# Power.net
KiCad netlist of a schematic drawn in Altium Designer
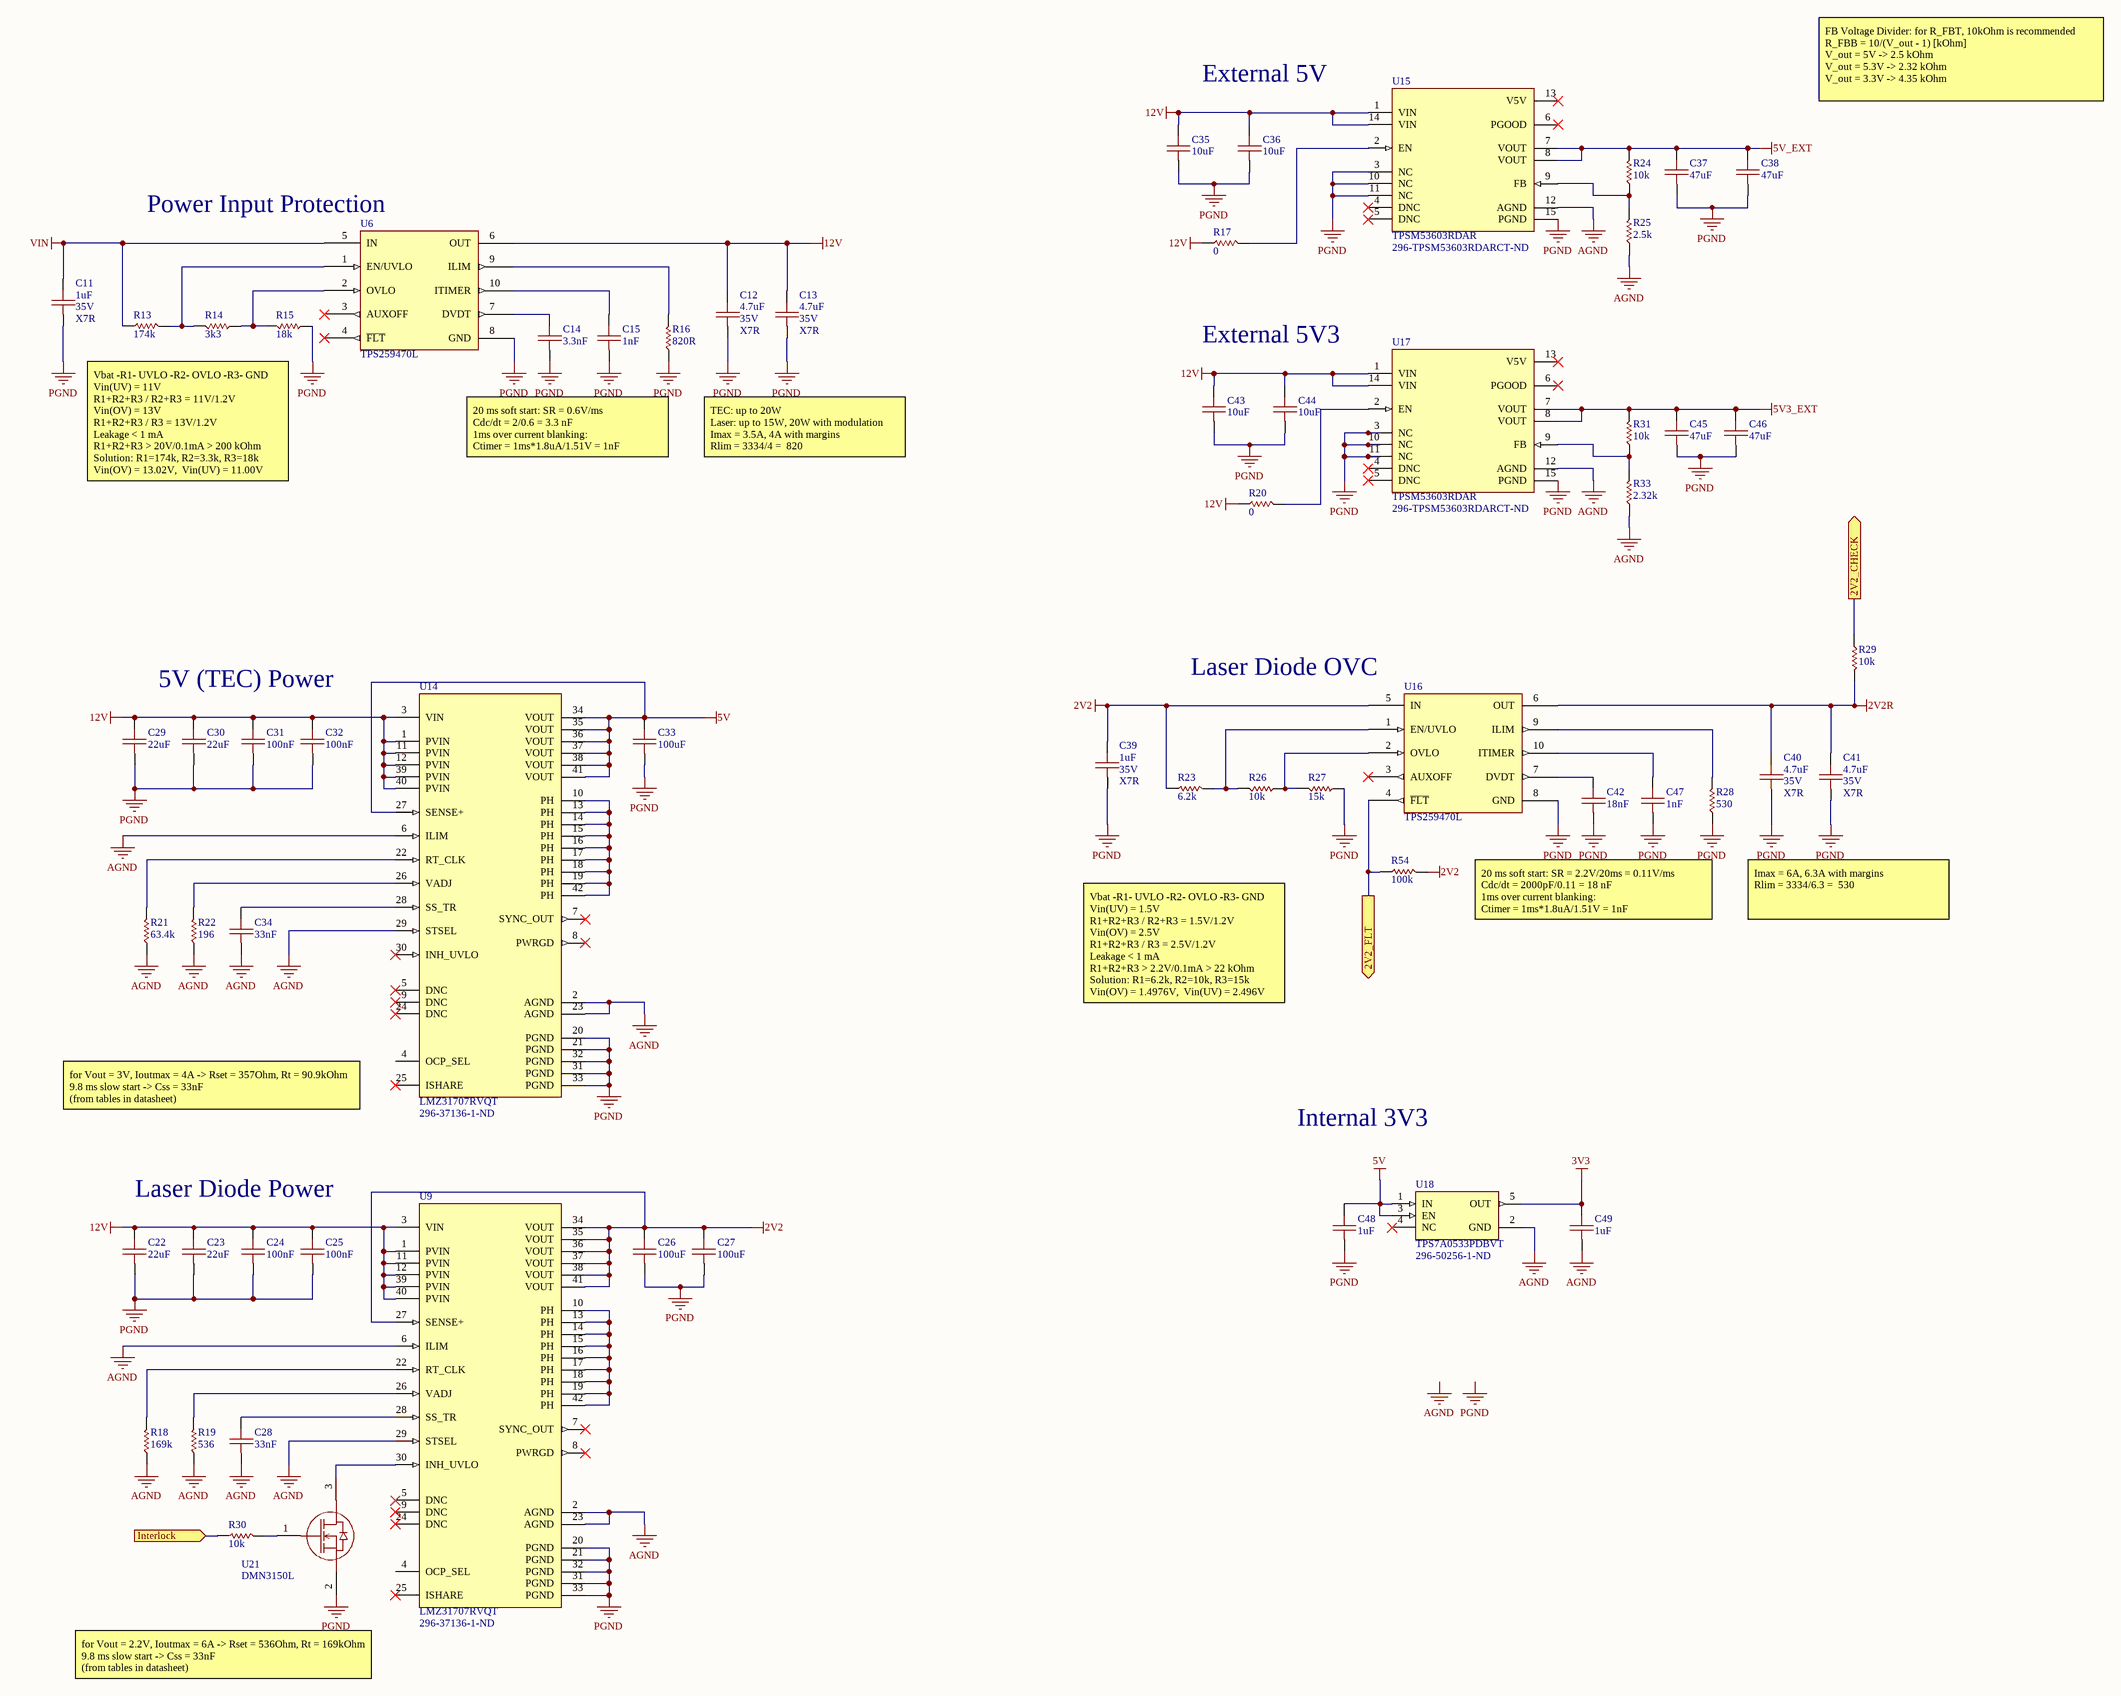
[diagram p0: Power.SchDoc]

(export (version "E")
  (design (tool "Eeschema 10.0.6"))
  (components
    (comp (ref "C11")
      (value "1uF")
      (footprint "0805 B")
      (description "805 Capacitor")
      (fields (field (name "VOLTAGE") "35V") (field (name "TYPE") "X7R"))
      (libsource (lib "PSSL3") (part "CAP 0805"))
    )
    (comp (ref "C12")
      (value "4.7uF")
      (footprint "0805 B")
      (description "805 Capacitor")
      (fields (field (name "VOLTAGE") "35V") (field (name "TYPE") "X7R"))
      (libsource (lib "PSSL3") (part "CAP 0805"))
    )
    (comp (ref "C13")
      (value "4.7uF")
      (footprint "0805 B")
      (description "805 Capacitor")
      (fields (field (name "VOLTAGE") "35V") (field (name "TYPE") "X7R"))
      (libsource (lib "PSSL3") (part "CAP 0805"))
    )
    (comp (ref "C14")
      (value "3.3nF")
      (footprint "0603 B")
      (description "603 Capacitor")
      (libsource (lib "PSSL3") (part "CAP 0603"))
    )
    (comp (ref "C15")
      (value "1nF")
      (footprint "0603 B")
      (description "603 Capacitor")
      (libsource (lib "PSSL3") (part "CAP 0603"))
    )
    (comp (ref "C22")
      (value "22uF")
      (footprint "1210")
      (description "1210 Capacitor")
      (libsource (lib "PSSL3") (part "CAP 1210"))
    )
    (comp (ref "C23")
      (value "22uF")
      (footprint "1210")
      (description "1210 Capacitor")
      (libsource (lib "PSSL3") (part "CAP 1210"))
    )
    (comp (ref "C24")
      (value "100nF")
      (footprint "0603 B")
      (description "603 Capacitor")
      (libsource (lib "PSSL3") (part "CAP 0603"))
    )
    (comp (ref "C25")
      (value "100nF")
      (footprint "0603 B")
      (description "603 Capacitor")
      (libsource (lib "PSSL3") (part "CAP 0603"))
    )
    (comp (ref "C26")
      (value "100uF")
      (footprint "1206 B")
      (description "1206 Capacitor")
      (libsource (lib "PSSL3") (part "CAP 1206"))
    )
    (comp (ref "C27")
      (value "100uF")
      (footprint "1206 B")
      (description "1206 Capacitor")
      (libsource (lib "PSSL3") (part "CAP 1206"))
    )
    (comp (ref "C28")
      (value "33nF")
      (footprint "0603 B")
      (description "603 Capacitor")
      (libsource (lib "PSSL3") (part "CAP 0603"))
    )
    (comp (ref "C29")
      (value "22uF")
      (footprint "1210")
      (description "1210 Capacitor")
      (libsource (lib "PSSL3") (part "CAP 1210"))
    )
    (comp (ref "C30")
      (value "22uF")
      (footprint "1210")
      (description "1210 Capacitor")
      (libsource (lib "PSSL3") (part "CAP 1210"))
    )
    (comp (ref "C31")
      (value "100nF")
      (footprint "0603 B")
      (description "603 Capacitor")
      (libsource (lib "PSSL3") (part "CAP 0603"))
    )
    (comp (ref "C32")
      (value "100nF")
      (footprint "0603 B")
      (description "603 Capacitor")
      (libsource (lib "PSSL3") (part "CAP 0603"))
    )
    (comp (ref "C33")
      (value "100uF")
      (footprint "1206 B")
      (description "1206 Capacitor")
      (libsource (lib "PSSL3") (part "CAP 1206"))
    )
    (comp (ref "C34")
      (value "33nF")
      (footprint "0603 B")
      (description "603 Capacitor")
      (libsource (lib "PSSL3") (part "CAP 0603"))
    )
    (comp (ref "C35")
      (value "10uF")
      (footprint "0603 B")
      (description "603 Capacitor")
      (libsource (lib "PSSL3") (part "CAP 0603"))
    )
    (comp (ref "C36")
      (value "10uF")
      (footprint "0603 B")
      (description "603 Capacitor")
      (libsource (lib "PSSL3") (part "CAP 0603"))
    )
    (comp (ref "C37")
      (value "47uF")
      (footprint "0603 B")
      (description "603 Capacitor")
      (libsource (lib "PSSL3") (part "CAP 0603"))
    )
    (comp (ref "C38")
      (value "47uF")
      (footprint "0603 B")
      (description "603 Capacitor")
      (libsource (lib "PSSL3") (part "CAP 0603"))
    )
    (comp (ref "C39")
      (value "1uF")
      (footprint "0805 B")
      (description "805 Capacitor")
      (fields (field (name "VOLTAGE") "35V") (field (name "TYPE") "X7R"))
      (libsource (lib "PSSL3") (part "CAP 0805"))
    )
    (comp (ref "C40")
      (value "4.7uF")
      (footprint "0805 B")
      (description "805 Capacitor")
      (fields (field (name "VOLTAGE") "35V") (field (name "TYPE") "X7R"))
      (libsource (lib "PSSL3") (part "CAP 0805"))
    )
    (comp (ref "C41")
      (value "4.7uF")
      (footprint "0805 B")
      (description "805 Capacitor")
      (fields (field (name "VOLTAGE") "35V") (field (name "TYPE") "X7R"))
      (libsource (lib "PSSL3") (part "CAP 0805"))
    )
    (comp (ref "C42")
      (value "18nF")
      (footprint "0603 B")
      (description "603 Capacitor")
      (libsource (lib "PSSL3") (part "CAP 0603"))
    )
    (comp (ref "C43")
      (value "10uF")
      (footprint "0603 B")
      (description "603 Capacitor")
      (libsource (lib "PSSL3") (part "CAP 0603"))
    )
    (comp (ref "C44")
      (value "10uF")
      (footprint "0603 B")
      (description "603 Capacitor")
      (libsource (lib "PSSL3") (part "CAP 0603"))
    )
    (comp (ref "C45")
      (value "47uF")
      (footprint "0603 B")
      (description "603 Capacitor")
      (libsource (lib "PSSL3") (part "CAP 0603"))
    )
    (comp (ref "C46")
      (value "47uF")
      (footprint "0603 B")
      (description "603 Capacitor")
      (libsource (lib "PSSL3") (part "CAP 0603"))
    )
    (comp (ref "C47")
      (value "1nF")
      (footprint "0603 B")
      (description "603 Capacitor")
      (libsource (lib "PSSL3") (part "CAP 0603"))
    )
    (comp (ref "C48")
      (value "1uF")
      (footprint "0603 B")
      (description "603 Capacitor")
      (libsource (lib "PSSL3") (part "CAP 0603"))
    )
    (comp (ref "C49")
      (value "1uF")
      (footprint "0603 B")
      (description "603 Capacitor")
      (libsource (lib "PSSL3") (part "CAP 0603"))
    )
    (comp (ref "R13")
      (value "174k")
      (footprint "0603")
      (description "603 Resistor")
      (libsource (lib "PSSL3") (part "RES 0603"))
    )
    (comp (ref "R14")
      (value "3k3")
      (footprint "0603")
      (description "603 Resistor")
      (libsource (lib "PSSL3") (part "RES 0603"))
    )
    (comp (ref "R15")
      (value "18k")
      (footprint "0603")
      (description "603 Resistor")
      (libsource (lib "PSSL3") (part "RES 0603"))
    )
    (comp (ref "R16")
      (value "820R")
      (footprint "0603")
      (description "603 Resistor")
      (libsource (lib "PSSL3") (part "RES 0603"))
    )
    (comp (ref "R17")
      (value "0")
      (footprint "0603")
      (description "603 Resistor")
      (libsource (lib "PSSL3") (part "RES 0603"))
    )
    (comp (ref "R18")
      (value "169k")
      (footprint "0805")
      (description "805 Resistor")
      (libsource (lib "PSSL3") (part "RES 0805"))
    )
    (comp (ref "R19")
      (value "536")
      (footprint "0805")
      (description "805 Resistor")
      (libsource (lib "PSSL3") (part "RES 0805"))
    )
    (comp (ref "R20")
      (value "0")
      (footprint "0603")
      (description "603 Resistor")
      (libsource (lib "PSSL3") (part "RES 0603"))
    )
    (comp (ref "R21")
      (value "63.4k")
      (footprint "0805")
      (description "805 Resistor")
      (libsource (lib "PSSL3") (part "RES 0805"))
    )
    (comp (ref "R22")
      (value "196")
      (footprint "0805")
      (description "805 Resistor")
      (libsource (lib "PSSL3") (part "RES 0805"))
    )
    (comp (ref "R23")
      (value "6.2k")
      (footprint "0603")
      (description "603 Resistor")
      (libsource (lib "PSSL3") (part "RES 0603"))
    )
    (comp (ref "R24")
      (value "10k")
      (footprint "0805")
      (description "805 Resistor")
      (libsource (lib "PSSL3") (part "RES 0805"))
    )
    (comp (ref "R25")
      (value "2.5k")
      (footprint "0805")
      (description "805 Resistor")
      (libsource (lib "PSSL3") (part "RES 0805"))
    )
    (comp (ref "R26")
      (value "10k")
      (footprint "0603")
      (description "603 Resistor")
      (libsource (lib "PSSL3") (part "RES 0603"))
    )
    (comp (ref "R27")
      (value "15k")
      (footprint "0603")
      (description "603 Resistor")
      (libsource (lib "PSSL3") (part "RES 0603"))
    )
    (comp (ref "R28")
      (value "530")
      (footprint "0603")
      (description "603 Resistor")
      (libsource (lib "PSSL3") (part "RES 0603"))
    )
    (comp (ref "R29")
      (value "10k")
      (footprint "0603")
      (description "603 Resistor")
      (libsource (lib "PSSL3") (part "RES 0603"))
    )
    (comp (ref "R30")
      (value "10k")
      (footprint "0603")
      (description "603 Resistor")
      (libsource (lib "PSSL3") (part "RES 0603"))
    )
    (comp (ref "R31")
      (value "10k")
      (footprint "0805")
      (description "805 Resistor")
      (libsource (lib "PSSL3") (part "RES 0805"))
    )
    (comp (ref "R33")
      (value "2.32k")
      (footprint "0805")
      (description "805 Resistor")
      (libsource (lib "PSSL3") (part "RES 0805"))
    )
    (comp (ref "R54")
      (value "100k")
      (footprint "0603")
      (description "603 Resistor")
      (libsource (lib "PSSL3") (part "RES 0603"))
    )
    (comp (ref "U6")
      (value "TPS259470L")
      (footprint "VQFN-HR 2x2")
      (description "2.7-23 V, 5.5 A, 28 mΩ True Reverse Current Blocking eFuse with Input Reverse Polarity Protection")
      (libsource (lib "PSSL3") (part "TPS259470L"))
    )
    (comp (ref "U9")
      (value "LMZ31707RVQT")
      (footprint "PB3QFN")
      (description "Non-Isolated DC/DC Converters 7A Power Module w/ 2.95V-17V Input")
      (fields
        (field (name "PARTNUMBER") "LMZ31707RVQR")
        (field (name "MANUFACTURER") "Texas Instruments")
        (field (name "SUPPLIER PART NUMBER 1") "296-37136-1-ND")
        (field (name "COPYRIGHT") "Copyright (C) 2018 Accelerated Designs. All rights reserved")
      )
      (libsource (lib "BeaconBoard") (part "LMZ31707RVQT"))
    )
    (comp (ref "U14")
      (value "LMZ31707RVQT")
      (footprint "PB3QFN")
      (description "Non-Isolated DC/DC Converters 7A Power Module w/ 2.95V-17V Input")
      (fields
        (field (name "PARTNUMBER") "LMZ31707RVQR")
        (field (name "MANUFACTURER") "Texas Instruments")
        (field (name "SUPPLIER PART NUMBER 1") "296-37136-1-ND")
        (field (name "COPYRIGHT") "Copyright (C) 2018 Accelerated Designs. All rights reserved")
      )
      (libsource (lib "BeaconBoard") (part "LMZ31707RVQT"))
    )
    (comp (ref "U15")
      (value "TPSM53603RDAR")
      (footprint "RDA0015A")
      (fields
        (field (name "MANUFACTURER") "Texas Instruments")
        (field (name "SUPPLIER PART NUMBER 1") "296-TPSM53603RDARCT-ND")
        (field (name "COPYRIGHT") "Copyright (C) 2018 Accelerated Designs. All rights reserved")
      )
      (libsource (lib "BeaconBoard") (part "TPSM53603RDAR"))
    )
    (comp (ref "U16")
      (value "TPS259470L")
      (footprint "VQFN-HR 2x2")
      (description "2.7-23 V, 5.5 A, 28 mΩ True Reverse Current Blocking eFuse with Input Reverse Polarity Protection")
      (libsource (lib "PSSL3") (part "TPS259470L"))
    )
    (comp (ref "U17")
      (value "TPSM53603RDAR")
      (footprint "RDA0015A")
      (fields
        (field (name "MANUFACTURER") "Texas Instruments")
        (field (name "SUPPLIER PART NUMBER 1") "296-TPSM53603RDARCT-ND")
        (field (name "COPYRIGHT") "Copyright (C) 2018 Accelerated Designs. All rights reserved")
      )
      (libsource (lib "BeaconBoard") (part "TPSM53603RDAR"))
    )
    (comp (ref "U18")
      (value "TPS7A0533PDBVT")
      (footprint "DBV0005A-MFG")
      (description "Linear Voltage Regulator IC Positive Fixed 1 Output 200mA SOT-23-5")
      (fields
        (field (name "PARTNUMBER") "TPS7A2050PDBVR")
        (field (name "MANUFACTURER") "Texas Instruments")
        (field (name "SUPPLIER PART NUMBER 1") "296-50256-1-ND")
        (field (name "COPYRIGHT") "Copyright (C) 2021 Accelerated Designs. All rights reserved")
      )
      (libsource (lib "BeaconBoard") (part "TPS7A0533PDBVT"))
    )
    (comp (ref "U21")
      (value "DMN3150L")
      (footprint "SOT-23")
      (description "Power-Transistor")
      (libsource (lib "PSSL3") (part "DMN3150L"))
    )
  )
  (nets
    (net (code "1") (name "/2V2_CHECK") (class "Default") (node (ref "R29") (pin "2") (pintype "passive")))
    (net (code "2") (name "/2V2_FLT") (class "Default")
      (node (ref "R54") (pin "2") (pintype "passive"))
      (node (ref "U16") (pin "4") (pinfunction "~{FLT}_4") (pintype "output"))
    )
    (net (code "3") (name "/Interlock") (class "Default") (node (ref "R30") (pin "2") (pintype "passive")))
    (net (code "4") (name "2V2") (class "Default")
      (node (ref "C26") (pin "2") (pintype "passive"))
      (node (ref "C27") (pin "2") (pintype "passive"))
      (node (ref "C39") (pin "2") (pintype "passive"))
      (node (ref "R23") (pin "2") (pintype "passive"))
      (node (ref "R54") (pin "1") (pintype "passive"))
      (node (ref "U16") (pin "5") (pinfunction "IN_5") (pintype "power_in"))
      (node (ref "U9") (pin "27") (pinfunction "SENSE+_27") (pintype "input"))
      (node (ref "U9") (pin "34") (pinfunction "VOUT_34") (pintype "power_in"))
      (node (ref "U9") (pin "35") (pinfunction "VOUT_35") (pintype "power_in"))
      (node (ref "U9") (pin "36") (pinfunction "VOUT_36") (pintype "power_in"))
      (node (ref "U9") (pin "37") (pinfunction "VOUT_37") (pintype "power_in"))
      (node (ref "U9") (pin "38") (pinfunction "VOUT_38") (pintype "power_in"))
      (node (ref "U9") (pin "41") (pinfunction "VOUT_41") (pintype "power_in"))
    )
    (net (code "5") (name "2V2R") (class "Default")
      (node (ref "C40") (pin "2") (pintype "passive"))
      (node (ref "C41") (pin "2") (pintype "passive"))
      (node (ref "R29") (pin "1") (pintype "passive"))
      (node (ref "U16") (pin "6") (pinfunction "OUT_6") (pintype "power_in"))
    )
    (net (code "6") (name "3V3") (class "Default")
      (node (ref "C49") (pin "2") (pintype "passive"))
      (node (ref "U18") (pin "5") (pinfunction "OUT_5") (pintype "output"))
    )
    (net (code "7") (name "5V") (class "Default")
      (node (ref "C33") (pin "2") (pintype "passive"))
      (node (ref "C48") (pin "2") (pintype "passive"))
      (node (ref "U14") (pin "27") (pinfunction "SENSE+_27") (pintype "input"))
      (node (ref "U14") (pin "34") (pinfunction "VOUT_34") (pintype "power_in"))
      (node (ref "U14") (pin "35") (pinfunction "VOUT_35") (pintype "power_in"))
      (node (ref "U14") (pin "36") (pinfunction "VOUT_36") (pintype "power_in"))
      (node (ref "U14") (pin "37") (pinfunction "VOUT_37") (pintype "power_in"))
      (node (ref "U14") (pin "38") (pinfunction "VOUT_38") (pintype "power_in"))
      (node (ref "U14") (pin "41") (pinfunction "VOUT_41") (pintype "power_in"))
      (node (ref "U18") (pin "1") (pinfunction "IN_1") (pintype "input"))
      (node (ref "U18") (pin "3") (pinfunction "EN_3") (pintype "input"))
    )
    (net (code "8") (name "5V3_EXT") (class "Default")
      (node (ref "C45") (pin "2") (pintype "passive"))
      (node (ref "C46") (pin "2") (pintype "passive"))
      (node (ref "R31") (pin "1") (pintype "passive"))
      (node (ref "U17") (pin "7") (pinfunction "VOUT_7") (pintype "power_in"))
      (node (ref "U17") (pin "8") (pinfunction "VOUT_8") (pintype "power_in"))
    )
    (net (code "9") (name "5V_EXT") (class "Default")
      (node (ref "C37") (pin "2") (pintype "passive"))
      (node (ref "C38") (pin "2") (pintype "passive"))
      (node (ref "R24") (pin "1") (pintype "passive"))
      (node (ref "U15") (pin "7") (pinfunction "VOUT_7") (pintype "power_in"))
      (node (ref "U15") (pin "8") (pinfunction "VOUT_8") (pintype "power_in"))
    )
    (net (code "10") (name "12V") (class "Default")
      (node (ref "C12") (pin "2") (pintype "passive"))
      (node (ref "C13") (pin "2") (pintype "passive"))
      (node (ref "C22") (pin "2") (pintype "passive"))
      (node (ref "C23") (pin "2") (pintype "passive"))
      (node (ref "C24") (pin "2") (pintype "passive"))
      (node (ref "C25") (pin "2") (pintype "passive"))
      (node (ref "C29") (pin "2") (pintype "passive"))
      (node (ref "C30") (pin "2") (pintype "passive"))
      (node (ref "C31") (pin "2") (pintype "passive"))
      (node (ref "C32") (pin "2") (pintype "passive"))
      (node (ref "C35") (pin "2") (pintype "passive"))
      (node (ref "C36") (pin "2") (pintype "passive"))
      (node (ref "C43") (pin "2") (pintype "passive"))
      (node (ref "C44") (pin "2") (pintype "passive"))
      (node (ref "R17") (pin "2") (pintype "passive"))
      (node (ref "R20") (pin "2") (pintype "passive"))
      (node (ref "U14") (pin "1") (pinfunction "PVIN_1") (pintype "power_in"))
      (node (ref "U14") (pin "11") (pinfunction "PVIN_11") (pintype "power_in"))
      (node (ref "U14") (pin "12") (pinfunction "PVIN_12") (pintype "power_in"))
      (node (ref "U14") (pin "3") (pinfunction "VIN_3") (pintype "power_in"))
      (node (ref "U14") (pin "39") (pinfunction "PVIN_39") (pintype "power_in"))
      (node (ref "U14") (pin "40") (pinfunction "PVIN_40") (pintype "power_in"))
      (node (ref "U15") (pin "1") (pinfunction "VIN_1") (pintype "power_in"))
      (node (ref "U15") (pin "14") (pinfunction "VIN_14") (pintype "power_in"))
      (node (ref "U17") (pin "1") (pinfunction "VIN_1") (pintype "power_in"))
      (node (ref "U17") (pin "14") (pinfunction "VIN_14") (pintype "power_in"))
      (node (ref "U6") (pin "6") (pinfunction "OUT_6") (pintype "power_in"))
      (node (ref "U9") (pin "1") (pinfunction "PVIN_1") (pintype "power_in"))
      (node (ref "U9") (pin "11") (pinfunction "PVIN_11") (pintype "power_in"))
      (node (ref "U9") (pin "12") (pinfunction "PVIN_12") (pintype "power_in"))
      (node (ref "U9") (pin "3") (pinfunction "VIN_3") (pintype "power_in"))
      (node (ref "U9") (pin "39") (pinfunction "PVIN_39") (pintype "power_in"))
      (node (ref "U9") (pin "40") (pinfunction "PVIN_40") (pintype "power_in"))
    )
    (net (code "11") (name "AGND") (class "Default")
      (node (ref "C28") (pin "1") (pintype "passive"))
      (node (ref "C34") (pin "1") (pintype "passive"))
      (node (ref "C49") (pin "1") (pintype "passive"))
      (node (ref "R18") (pin "2") (pintype "passive"))
      (node (ref "R19") (pin "2") (pintype "passive"))
      (node (ref "R21") (pin "2") (pintype "passive"))
      (node (ref "R22") (pin "2") (pintype "passive"))
      (node (ref "R25") (pin "2") (pintype "passive"))
      (node (ref "R33") (pin "2") (pintype "passive"))
      (node (ref "U14") (pin "2") (pinfunction "AGND_2") (pintype "power_in"))
      (node (ref "U14") (pin "23") (pinfunction "AGND_23") (pintype "power_in"))
      (node (ref "U14") (pin "29") (pinfunction "STSEL_29") (pintype "input"))
      (node (ref "U14") (pin "6") (pinfunction "ILIM_6") (pintype "input"))
      (node (ref "U15") (pin "12") (pinfunction "AGND_12") (pintype "power_in"))
      (node (ref "U17") (pin "12") (pinfunction "AGND_12") (pintype "power_in"))
      (node (ref "U18") (pin "2") (pinfunction "GND_2") (pintype "power_in"))
      (node (ref "U9") (pin "2") (pinfunction "AGND_2") (pintype "power_in"))
      (node (ref "U9") (pin "23") (pinfunction "AGND_23") (pintype "power_in"))
      (node (ref "U9") (pin "29") (pinfunction "STSEL_29") (pintype "input"))
      (node (ref "U9") (pin "6") (pinfunction "ILIM_6") (pintype "input"))
    )
    (net (code "12") (name "Net-(U6-DVDT)") (class "Default")
      (node (ref "C14") (pin "2") (pintype "passive"))
      (node (ref "U6") (pin "7") (pinfunction "DVDT_7") (pintype "output"))
    )
    (net (code "13") (name "Net-(U6-EN{slash}UVLO)") (class "Default")
      (node (ref "R13") (pin "1") (pintype "passive"))
      (node (ref "R14") (pin "1") (pintype "passive"))
      (node (ref "U6") (pin "1") (pinfunction "EN/UVLO_1") (pintype "input"))
    )
    (net (code "14") (name "Net-(U6-ILIM)") (class "Default")
      (node (ref "R16") (pin "1") (pintype "passive"))
      (node (ref "U6") (pin "9") (pinfunction "ILIM_9") (pintype "output"))
    )
    (net (code "15") (name "Net-(U6-ITIMER)") (class "Default")
      (node (ref "C15") (pin "2") (pintype "passive"))
      (node (ref "U6") (pin "10") (pinfunction "ITIMER_10") (pintype "output"))
    )
    (net (code "16") (name "Net-(U6-OVLO)") (class "Default")
      (node (ref "R14") (pin "2") (pintype "passive"))
      (node (ref "R15") (pin "1") (pintype "passive"))
      (node (ref "U6") (pin "2") (pinfunction "OVLO_2") (pintype "input"))
    )
    (net (code "17") (name "Net-(U9-PH-Pad10)") (class "Default")
      (node (ref "U9") (pin "10") (pinfunction "PH_10") (pintype "power_in"))
      (node (ref "U9") (pin "13") (pinfunction "PH_13") (pintype "power_in"))
      (node (ref "U9") (pin "14") (pinfunction "PH_14") (pintype "power_in"))
      (node (ref "U9") (pin "15") (pinfunction "PH_15") (pintype "power_in"))
      (node (ref "U9") (pin "16") (pinfunction "PH_16") (pintype "power_in"))
      (node (ref "U9") (pin "17") (pinfunction "PH_17") (pintype "power_in"))
      (node (ref "U9") (pin "18") (pinfunction "PH_18") (pintype "power_in"))
      (node (ref "U9") (pin "19") (pinfunction "PH_19") (pintype "power_in"))
      (node (ref "U9") (pin "42") (pinfunction "PH_42") (pintype "power_in"))
    )
    (net (code "18") (name "Net-(U9-RT_CLK)") (class "Default")
      (node (ref "R18") (pin "1") (pintype "passive"))
      (node (ref "U9") (pin "22") (pinfunction "RT_CLK_22") (pintype "input"))
    )
    (net (code "19") (name "Net-(U9-SS_TR)") (class "Default")
      (node (ref "C28") (pin "2") (pintype "passive"))
      (node (ref "U9") (pin "28") (pinfunction "SS_TR_28") (pintype "input"))
    )
    (net (code "20") (name "Net-(U9-VADJ)") (class "Default")
      (node (ref "R19") (pin "1") (pintype "passive"))
      (node (ref "U9") (pin "26") (pinfunction "VADJ_26") (pintype "input"))
    )
    (net (code "21") (name "Net-(U14-PH-Pad10)") (class "Default")
      (node (ref "U14") (pin "10") (pinfunction "PH_10") (pintype "power_in"))
      (node (ref "U14") (pin "13") (pinfunction "PH_13") (pintype "power_in"))
      (node (ref "U14") (pin "14") (pinfunction "PH_14") (pintype "power_in"))
      (node (ref "U14") (pin "15") (pinfunction "PH_15") (pintype "power_in"))
      (node (ref "U14") (pin "16") (pinfunction "PH_16") (pintype "power_in"))
      (node (ref "U14") (pin "17") (pinfunction "PH_17") (pintype "power_in"))
      (node (ref "U14") (pin "18") (pinfunction "PH_18") (pintype "power_in"))
      (node (ref "U14") (pin "19") (pinfunction "PH_19") (pintype "power_in"))
      (node (ref "U14") (pin "42") (pinfunction "PH_42") (pintype "power_in"))
    )
    (net (code "22") (name "Net-(U14-RT_CLK)") (class "Default")
      (node (ref "R21") (pin "1") (pintype "passive"))
      (node (ref "U14") (pin "22") (pinfunction "RT_CLK_22") (pintype "input"))
    )
    (net (code "23") (name "Net-(U14-SS_TR)") (class "Default")
      (node (ref "C34") (pin "2") (pintype "passive"))
      (node (ref "U14") (pin "28") (pinfunction "SS_TR_28") (pintype "input"))
    )
    (net (code "24") (name "Net-(U14-VADJ)") (class "Default")
      (node (ref "R22") (pin "1") (pintype "passive"))
      (node (ref "U14") (pin "26") (pinfunction "VADJ_26") (pintype "input"))
    )
    (net (code "25") (name "Net-(U15-EN)") (class "Default")
      (node (ref "R17") (pin "1") (pintype "passive"))
      (node (ref "U15") (pin "2") (pinfunction "EN_2") (pintype "input"))
    )
    (net (code "26") (name "Net-(U15-FB)") (class "Default")
      (node (ref "R24") (pin "2") (pintype "passive"))
      (node (ref "R25") (pin "1") (pintype "passive"))
      (node (ref "U15") (pin "9") (pinfunction "FB_9") (pintype "input"))
    )
    (net (code "27") (name "Net-(U16-DVDT)") (class "Default")
      (node (ref "C42") (pin "2") (pintype "passive"))
      (node (ref "U16") (pin "7") (pinfunction "DVDT_7") (pintype "output"))
    )
    (net (code "28") (name "Net-(U16-EN{slash}UVLO)") (class "Default")
      (node (ref "R23") (pin "1") (pintype "passive"))
      (node (ref "R26") (pin "1") (pintype "passive"))
      (node (ref "U16") (pin "1") (pinfunction "EN/UVLO_1") (pintype "input"))
    )
    (net (code "29") (name "Net-(U16-ILIM)") (class "Default")
      (node (ref "R28") (pin "1") (pintype "passive"))
      (node (ref "U16") (pin "9") (pinfunction "ILIM_9") (pintype "output"))
    )
    (net (code "30") (name "Net-(U16-ITIMER)") (class "Default")
      (node (ref "C47") (pin "2") (pintype "passive"))
      (node (ref "U16") (pin "10") (pinfunction "ITIMER_10") (pintype "output"))
    )
    (net (code "31") (name "Net-(U16-OVLO)") (class "Default")
      (node (ref "R26") (pin "2") (pintype "passive"))
      (node (ref "R27") (pin "1") (pintype "passive"))
      (node (ref "U16") (pin "2") (pinfunction "OVLO_2") (pintype "input"))
    )
    (net (code "32") (name "Net-(U17-EN)") (class "Default")
      (node (ref "R20") (pin "1") (pintype "passive"))
      (node (ref "U17") (pin "2") (pinfunction "EN_2") (pintype "input"))
    )
    (net (code "33") (name "Net-(U17-FB)") (class "Default")
      (node (ref "R31") (pin "2") (pintype "passive"))
      (node (ref "R33") (pin "1") (pintype "passive"))
      (node (ref "U17") (pin "9") (pinfunction "FB_9") (pintype "input"))
    )
    (net (code "34") (name "Net-(U21-D)") (class "Default")
      (node (ref "U21") (pin "3") (pinfunction "D_3") (pintype "power_in"))
      (node (ref "U9") (pin "30") (pinfunction "INH_UVLO_30") (pintype "input"))
    )
    (net (code "35") (name "Net-(U21-G)") (class "Default")
      (node (ref "R30") (pin "1") (pintype "passive"))
      (node (ref "U21") (pin "1") (pinfunction "G_1") (pintype "power_in"))
    )
    (net (code "36") (name "PGND") (class "Default")
      (node (ref "C11") (pin "1") (pintype "passive"))
      (node (ref "C12") (pin "1") (pintype "passive"))
      (node (ref "C13") (pin "1") (pintype "passive"))
      (node (ref "C14") (pin "1") (pintype "passive"))
      (node (ref "C15") (pin "1") (pintype "passive"))
      (node (ref "C22") (pin "1") (pintype "passive"))
      (node (ref "C23") (pin "1") (pintype "passive"))
      (node (ref "C24") (pin "1") (pintype "passive"))
      (node (ref "C25") (pin "1") (pintype "passive"))
      (node (ref "C26") (pin "1") (pintype "passive"))
      (node (ref "C27") (pin "1") (pintype "passive"))
      (node (ref "C29") (pin "1") (pintype "passive"))
      (node (ref "C30") (pin "1") (pintype "passive"))
      (node (ref "C31") (pin "1") (pintype "passive"))
      (node (ref "C32") (pin "1") (pintype "passive"))
      (node (ref "C33") (pin "1") (pintype "passive"))
      (node (ref "C35") (pin "1") (pintype "passive"))
      (node (ref "C36") (pin "1") (pintype "passive"))
      (node (ref "C37") (pin "1") (pintype "passive"))
      (node (ref "C38") (pin "1") (pintype "passive"))
      (node (ref "C39") (pin "1") (pintype "passive"))
      (node (ref "C40") (pin "1") (pintype "passive"))
      (node (ref "C41") (pin "1") (pintype "passive"))
      (node (ref "C42") (pin "1") (pintype "passive"))
      (node (ref "C43") (pin "1") (pintype "passive"))
      (node (ref "C44") (pin "1") (pintype "passive"))
      (node (ref "C45") (pin "1") (pintype "passive"))
      (node (ref "C46") (pin "1") (pintype "passive"))
      (node (ref "C47") (pin "1") (pintype "passive"))
      (node (ref "C48") (pin "1") (pintype "passive"))
      (node (ref "R15") (pin "2") (pintype "passive"))
      (node (ref "R16") (pin "2") (pintype "passive"))
      (node (ref "R27") (pin "2") (pintype "passive"))
      (node (ref "R28") (pin "2") (pintype "passive"))
      (node (ref "U14") (pin "20") (pinfunction "PGND_20") (pintype "power_in"))
      (node (ref "U14") (pin "21") (pinfunction "PGND_21") (pintype "power_in"))
      (node (ref "U14") (pin "31") (pinfunction "PGND_31") (pintype "power_in"))
      (node (ref "U14") (pin "32") (pinfunction "PGND_32") (pintype "power_in"))
      (node (ref "U14") (pin "33") (pinfunction "PGND_33") (pintype "power_in"))
      (node (ref "U15") (pin "10") (pinfunction "NC_10") (pintype "passive"))
      (node (ref "U15") (pin "11") (pinfunction "NC_11") (pintype "passive"))
      (node (ref "U15") (pin "15") (pinfunction "PGND_15") (pintype "power_in"))
      (node (ref "U15") (pin "3") (pinfunction "NC_3") (pintype "passive"))
      (node (ref "U16") (pin "8") (pinfunction "GND_8") (pintype "power_in"))
      (node (ref "U17") (pin "10") (pinfunction "NC_10") (pintype "passive"))
      (node (ref "U17") (pin "11") (pinfunction "NC_11") (pintype "passive"))
      (node (ref "U17") (pin "15") (pinfunction "PGND_15") (pintype "power_in"))
      (node (ref "U17") (pin "3") (pinfunction "NC_3") (pintype "passive"))
      (node (ref "U21") (pin "2") (pinfunction "S_2") (pintype "power_in"))
      (node (ref "U6") (pin "8") (pinfunction "GND_8") (pintype "power_in"))
      (node (ref "U9") (pin "20") (pinfunction "PGND_20") (pintype "power_in"))
      (node (ref "U9") (pin "21") (pinfunction "PGND_21") (pintype "power_in"))
      (node (ref "U9") (pin "31") (pinfunction "PGND_31") (pintype "power_in"))
      (node (ref "U9") (pin "32") (pinfunction "PGND_32") (pintype "power_in"))
      (node (ref "U9") (pin "33") (pinfunction "PGND_33") (pintype "power_in"))
    )
    (net (code "37") (name "VIN") (class "Default")
      (node (ref "C11") (pin "2") (pintype "passive"))
      (node (ref "R13") (pin "2") (pintype "passive"))
      (node (ref "U6") (pin "5") (pinfunction "IN_5") (pintype "power_in"))
    )
    (net (code "38") (name "unconnected-(U6-AUXOFF-Pad3)") (class "Default")
      (node (ref "U6") (pin "3") (pinfunction "AUXOFF_3") (pintype "output+no_connect"))
    )
    (net (code "39") (name "unconnected-(U6-~{FLT}-Pad4)") (class "Default")
      (node (ref "U6") (pin "4") (pinfunction "~{FLT}_4") (pintype "output+no_connect"))
    )
    (net (code "40") (name "unconnected-(U9-DNC-Pad5)") (class "Default")
      (node (ref "U9") (pin "5") (pinfunction "DNC_5") (pintype "passive+no_connect"))
    )
    (net (code "41") (name "unconnected-(U9-DNC-Pad9)") (class "Default")
      (node (ref "U9") (pin "9") (pinfunction "DNC_9") (pintype "passive+no_connect"))
    )
    (net (code "42") (name "unconnected-(U9-DNC-Pad24)") (class "Default")
      (node (ref "U9") (pin "24") (pinfunction "DNC_24") (pintype "passive+no_connect"))
    )
    (net (code "43") (name "unconnected-(U9-ISHARE-Pad25)") (class "Default")
      (node (ref "U9") (pin "25") (pinfunction "ISHARE_25") (pintype "passive+no_connect"))
    )
    (net (code "44") (name "unconnected-(U9-OCP_SEL-Pad4)") (class "Default")
      (node (ref "U9") (pin "4") (pinfunction "OCP_SEL_4") (pintype "passive"))
    )
    (net (code "45") (name "unconnected-(U9-PWRGD-Pad8)") (class "Default")
      (node (ref "U9") (pin "8") (pinfunction "PWRGD_8") (pintype "output+no_connect"))
    )
    (net (code "46") (name "unconnected-(U9-SYNC_OUT-Pad7)") (class "Default")
      (node (ref "U9") (pin "7") (pinfunction "SYNC_OUT_7") (pintype "output+no_connect"))
    )
    (net (code "47") (name "unconnected-(U14-DNC-Pad5)") (class "Default")
      (node (ref "U14") (pin "5") (pinfunction "DNC_5") (pintype "passive+no_connect"))
    )
    (net (code "48") (name "unconnected-(U14-DNC-Pad9)") (class "Default")
      (node (ref "U14") (pin "9") (pinfunction "DNC_9") (pintype "passive+no_connect"))
    )
    (net (code "49") (name "unconnected-(U14-DNC-Pad24)") (class "Default")
      (node (ref "U14") (pin "24") (pinfunction "DNC_24") (pintype "passive+no_connect"))
    )
    (net (code "50") (name "unconnected-(U14-INH_UVLO-Pad30)") (class "Default")
      (node (ref "U14") (pin "30") (pinfunction "INH_UVLO_30") (pintype "input+no_connect"))
    )
    (net (code "51") (name "unconnected-(U14-ISHARE-Pad25)") (class "Default")
      (node (ref "U14") (pin "25") (pinfunction "ISHARE_25") (pintype "passive+no_connect"))
    )
    (net (code "52") (name "unconnected-(U14-OCP_SEL-Pad4)") (class "Default")
      (node (ref "U14") (pin "4") (pinfunction "OCP_SEL_4") (pintype "passive"))
    )
    (net (code "53") (name "unconnected-(U14-PWRGD-Pad8)") (class "Default")
      (node (ref "U14") (pin "8") (pinfunction "PWRGD_8") (pintype "output+no_connect"))
    )
    (net (code "54") (name "unconnected-(U14-SYNC_OUT-Pad7)") (class "Default")
      (node (ref "U14") (pin "7") (pinfunction "SYNC_OUT_7") (pintype "output+no_connect"))
    )
    (net (code "55") (name "unconnected-(U15-DNC-Pad4)") (class "Default")
      (node (ref "U15") (pin "4") (pinfunction "DNC_4") (pintype "passive+no_connect"))
    )
    (net (code "56") (name "unconnected-(U15-DNC-Pad5)") (class "Default")
      (node (ref "U15") (pin "5") (pinfunction "DNC_5") (pintype "passive+no_connect"))
    )
    (net (code "57") (name "unconnected-(U15-PGOOD-Pad6)") (class "Default")
      (node (ref "U15") (pin "6") (pinfunction "PGOOD_6") (pintype "open_collector+no_connect"))
    )
    (net (code "58") (name "unconnected-(U15-V5V-Pad13)") (class "Default")
      (node (ref "U15") (pin "13") (pinfunction "V5V_13") (pintype "power_in+no_connect"))
    )
    (net (code "59") (name "unconnected-(U16-AUXOFF-Pad3)") (class "Default")
      (node (ref "U16") (pin "3") (pinfunction "AUXOFF_3") (pintype "output+no_connect"))
    )
    (net (code "60") (name "unconnected-(U17-DNC-Pad4)") (class "Default")
      (node (ref "U17") (pin "4") (pinfunction "DNC_4") (pintype "passive+no_connect"))
    )
    (net (code "61") (name "unconnected-(U17-DNC-Pad5)") (class "Default")
      (node (ref "U17") (pin "5") (pinfunction "DNC_5") (pintype "passive+no_connect"))
    )
    (net (code "62") (name "unconnected-(U17-PGOOD-Pad6)") (class "Default")
      (node (ref "U17") (pin "6") (pinfunction "PGOOD_6") (pintype "open_collector+no_connect"))
    )
    (net (code "63") (name "unconnected-(U17-V5V-Pad13)") (class "Default")
      (node (ref "U17") (pin "13") (pinfunction "V5V_13") (pintype "power_in+no_connect"))
    )
    (net (code "64") (name "unconnected-(U18-NC-Pad4)") (class "Default")
      (node (ref "U18") (pin "4") (pinfunction "NC_4") (pintype "passive+no_connect"))
    )
  )
)
